# power.net
KiCad netlist of a schematic drawn in Altium Designer
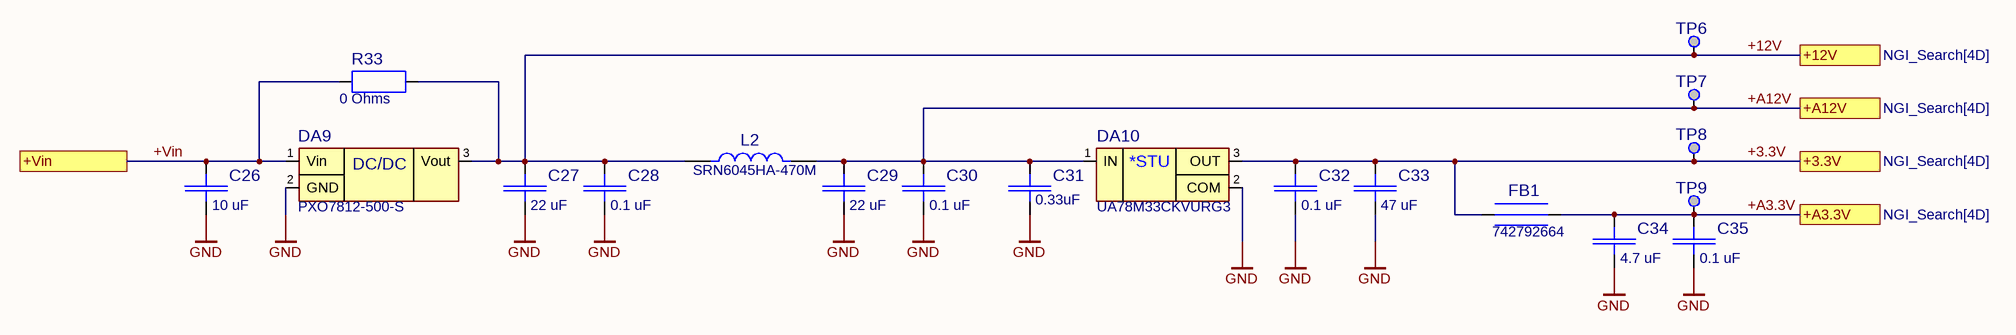
[diagram p0: power.SchDoc]

(export (version "E")
  (design (tool "Eeschema 10.0.6"))
  (components
    (comp (ref "C26")
      (value "10 uF")
      (footprint "Capacitor0805_THICKNESS1.45")
      (description "Multilayer Ceramic Capacitors MLCC - SMD/SMT 10 uF 35 VDC 10% 0805 X5R")
      (fields (field (name "TOLERANCE") "10%") (field (name "MANUFACTURERPARTNUMBER") "GRM21BR6YA106KE43K"))
      (libsource (lib "NGI_Search") (part "GRM21BR6YA106KE43K"))
    )
    (comp (ref "C27")
      (value "22 uF")
      (footprint "Capacitor1206_THICKNESS1.6")
      (description "Multilayer Ceramic Capacitors MLCC - SMD/SMT 1206 35V 22uF X5R 20% T: 1.6mm")
      (fields
        (field (name "MANUFACTURER") "TDK")
        (field (name "MANUFACTURERPARTNUMBER") "C3216X5R1V226M160AC")
      )
      (libsource (lib "NGI_Search") (part "C3216X5R1V226M160AC"))
    )
    (comp (ref "C28")
      (value "0.1 uF")
      (footprint "Capacitor0805_THICKNESS0.8")
      (description "Multilayer Ceramic Capacitors MLCC - SMD/SMT 100nF+/-10% 50V X7R 0805")
      (fields (field (name "TOLERANCE") "10%") (field (name "MANUFACTURERPARTNUMBER") "CL21B104KBCNNWC"))
      (libsource (lib "NGI_Search") (part "CL21B104KBCNNWC"))
    )
    (comp (ref "C29")
      (value "22 uF")
      (footprint "Capacitor1206_THICKNESS1.6")
      (description "Multilayer Ceramic Capacitors MLCC - SMD/SMT 1206 35V 22uF X5R 20% T: 1.6mm")
      (fields
        (field (name "MANUFACTURER") "TDK")
        (field (name "MANUFACTURERPARTNUMBER") "C3216X5R1V226M160AC")
      )
      (libsource (lib "NGI_Search") (part "C3216X5R1V226M160AC"))
    )
    (comp (ref "C30")
      (value "0.1 uF")
      (footprint "Capacitor0805_THICKNESS0.8")
      (description "Multilayer Ceramic Capacitors MLCC - SMD/SMT 100nF+/-10% 50V X7R 0805")
      (fields (field (name "TOLERANCE") "10%") (field (name "MANUFACTURERPARTNUMBER") "CL21B104KBCNNWC"))
      (libsource (lib "NGI_Search") (part "CL21B104KBCNNWC"))
    )
    (comp (ref "C31")
      (value "0.33uF")
      (footprint "Capacitor0805_THICKNESS1.25")
      (description "Multilayer Ceramic Capacitors MLCC - SMD/SMT 25V 0.33uF X7R 0805 10%")
      (fields
        (field (name "MANUFACTURER") "YAGEO")
        (field (name "MANUFACTURERPARTNUMBER") "CC0805KKX7R8BB334")
      )
      (libsource (lib "NGI_Search") (part "CC0805KKX7R8BB334"))
    )
    (comp (ref "C32")
      (value "0.1 uF")
      (footprint "Capacitor0805_THICKNESS0.8")
      (description "Multilayer Ceramic Capacitors MLCC - SMD/SMT 100nF+/-10% 50V X7R 0805")
      (fields (field (name "TOLERANCE") "10%") (field (name "MANUFACTURERPARTNUMBER") "CL21B104KBCNNWC"))
      (libsource (lib "NGI_Search") (part "CL21B104KBCNNWC"))
    )
    (comp (ref "C33")
      (value "47 uF")
      (footprint "Capacitor0805_THICKNESS1.25")
      (description "Multilayer Ceramic Capacitors MLCC - SMD/SMT 47 uF 10 VDC 20% 0805 X5R")
      (fields
        (field (name "MANUFACTURER") "Murata")
        (field (name "MANUFACTURERPARTNUMBER") "GRM21BR61A476ME15K")
      )
      (libsource (lib "NGI_Search") (part "GRM21BR61A476ME15K"))
    )
    (comp (ref "C34")
      (value "4.7 uF")
      (footprint "Capacitor0805_THICKNESS1.25")
      (description "Multilayer Ceramic Capacitors MLCC - SMD/SMT 4.7uF+/-10% 25V X5R 0805")
      (fields
        (field (name "MANUFACTURER") "Samsung Electro-Mechanics")
        (field (name "MANUFACTURERPARTNUMBER") "CL21A475KAQNNNF")
      )
      (libsource (lib "NGI_Search") (part "CL21A475KAQNNNF"))
    )
    (comp (ref "C35")
      (value "0.1 uF")
      (footprint "Capacitor0805_THICKNESS0.8")
      (description "Multilayer Ceramic Capacitors MLCC - SMD/SMT 100nF+/-10% 50V X7R 0805")
      (fields (field (name "TOLERANCE") "10%") (field (name "MANUFACTURERPARTNUMBER") "CL21B104KBCNNWC"))
      (libsource (lib "NGI_Search") (part "CL21B104KBCNNWC"))
    )
    (comp (ref "DA9")
      (value "PXO7812-500-S")
      (footprint "PXO7812-500-S_POSITIVEOUTPUT")
      (description "Non-Isolated DC/DC Converters dc-dc non-isolated, 0.5 A, 15-36 Vdc input, 12 Vdc output, SIP")
      (fields
        (field (name "MANUFACTURER") "CUI Inc.")
        (field (name "MOUSER PART NUMBER") "490-PXO7812-500-S")
      )
      (libsource (lib "NGI_Search") (part "PXO7812-500-S"))
    )
    (comp (ref "DA10")
      (value "UA78M33CKVURG3")
      (footprint "TO-252 3pin THICKNESS2.52")
      (description "Linear Voltage Regulators 3.3 V 500mA Fix Pos Voltage Regulator")
      (fields
        (field (name "MANUFACTURER") "Texas Instruments")
        (field (name "MOUSER PART NUMBER") "595-UA78M33CKVURG3")
      )
      (libsource (lib "NGI_Search") (part "UA78M33CKVURG3"))
    )
    (comp (ref "FB1")
      (value "742792664")
      (footprint "742792664_Ferrite Beads_0603")
      (description "Ferrite Beads WE-CBF 0603 100MHz 1000Ohm 300mA AEC-Q200")
      (fields
        (field (name "MANUFACTURER") "Wurth Elektronik")
        (field (name "MOUSER PART NUMBER") "710-742792664")
      )
      (libsource (lib "NGI_Search") (part "742792664"))
    )
    (comp (ref "L2")
      (value "SRN6045HA-470M")
      (footprint "SRN6045HA-470M")
      (description "Power Inductors - SMD Ind,6x6x4.7mm,47uH+/-20%,1A,semi-shd")
      (fields (field (name "MANUFACTURER") "Bourns") (field (name "MOUSER PART NUMBER") "652-SRN6045HA-470M"))
      (libsource (lib "NGI_Search") (part "SRN6045HA-470M"))
    )
    (comp (ref "R33")
      (value "0 Ohms")
      (footprint "Resistor1206_THICKNESS0.65")
      (description "Thick Film Resistors 0 Ohms 250 mW 1206 1%")
      (fields (field (name "MANUFACTURER") "YAGEO") (field (name "MANUFACTURERPARTNUMBER") "RC1206FR-070RL"))
      (libsource (lib "NGI_Search") (part "RC1206FR-070RL"))
    )
    (comp (ref "TP6")
      (value "test point")
      (footprint "test point")
      (libsource (lib "NGI_Search") (part "test point"))
    )
    (comp (ref "TP7")
      (value "test point")
      (footprint "test point")
      (libsource (lib "NGI_Search") (part "test point"))
    )
    (comp (ref "TP8")
      (value "test point")
      (footprint "test point")
      (libsource (lib "NGI_Search") (part "test point"))
    )
    (comp (ref "TP9")
      (value "test point")
      (footprint "test point")
      (libsource (lib "NGI_Search") (part "test point"))
    )
  )
  (nets
    (net (code "1") (name "/+3.3V") (class "Default")
      (node (ref "C32") (pin "2") (pinfunction "2_2") (pintype "passive"))
      (node (ref "C33") (pin "2") (pinfunction "2_2") (pintype "passive"))
      (node (ref "DA10") (pin "3") (pinfunction "OUT_3") (pintype "passive"))
      (node (ref "FB1") (pin "1") (pinfunction "1_1") (pintype "passive"))
      (node (ref "TP8") (pin "1") (pinfunction "1_1") (pintype "passive"))
    )
    (net (code "2") (name "/+12V") (class "Default")
      (node (ref "C27") (pin "2") (pinfunction "2_2") (pintype "passive"))
      (node (ref "C28") (pin "2") (pinfunction "2_2") (pintype "passive"))
      (node (ref "DA9") (pin "3") (pinfunction "Vout_3") (pintype "passive"))
      (node (ref "L2") (pin "1") (pinfunction "1_1") (pintype "passive"))
      (node (ref "R33") (pin "2") (pinfunction "2_2") (pintype "passive"))
      (node (ref "TP6") (pin "1") (pinfunction "1_1") (pintype "passive"))
    )
    (net (code "3") (name "/+A3.3V") (class "Default")
      (node (ref "C34") (pin "2") (pinfunction "2_2") (pintype "passive"))
      (node (ref "C35") (pin "2") (pinfunction "2_2") (pintype "passive"))
      (node (ref "FB1") (pin "2") (pinfunction "2_2") (pintype "passive"))
      (node (ref "TP9") (pin "1") (pinfunction "1_1") (pintype "passive"))
    )
    (net (code "4") (name "/+A12V") (class "Default")
      (node (ref "C29") (pin "2") (pinfunction "2_2") (pintype "passive"))
      (node (ref "C30") (pin "2") (pinfunction "2_2") (pintype "passive"))
      (node (ref "C31") (pin "2") (pinfunction "2_2") (pintype "passive"))
      (node (ref "DA10") (pin "1") (pinfunction "IN_1") (pintype "passive"))
      (node (ref "L2") (pin "2") (pinfunction "2_2") (pintype "passive"))
      (node (ref "TP7") (pin "1") (pinfunction "1_1") (pintype "passive"))
    )
    (net (code "5") (name "/+Vin") (class "Default")
      (node (ref "C26") (pin "2") (pinfunction "2_2") (pintype "passive"))
      (node (ref "DA9") (pin "1") (pinfunction "Vin_1") (pintype "passive"))
      (node (ref "R33") (pin "1") (pinfunction "1_1") (pintype "passive"))
    )
    (net (code "6") (name "GND") (class "Default")
      (node (ref "C26") (pin "1") (pinfunction "1_1") (pintype "passive"))
      (node (ref "C27") (pin "1") (pinfunction "1_1") (pintype "passive"))
      (node (ref "C28") (pin "1") (pinfunction "1_1") (pintype "passive"))
      (node (ref "C29") (pin "1") (pinfunction "1_1") (pintype "passive"))
      (node (ref "C30") (pin "1") (pinfunction "1_1") (pintype "passive"))
      (node (ref "C31") (pin "1") (pinfunction "1_1") (pintype "passive"))
      (node (ref "C32") (pin "1") (pinfunction "1_1") (pintype "passive"))
      (node (ref "C33") (pin "1") (pinfunction "1_1") (pintype "passive"))
      (node (ref "C34") (pin "1") (pinfunction "1_1") (pintype "passive"))
      (node (ref "C35") (pin "1") (pinfunction "1_1") (pintype "passive"))
      (node (ref "DA10") (pin "2") (pinfunction "COM_2") (pintype "power_in"))
      (node (ref "DA9") (pin "2") (pinfunction "GND_2") (pintype "power_in"))
    )
  )
)
